# Panel_protection.net
KiCad netlist of a schematic drawn in Altium Designer
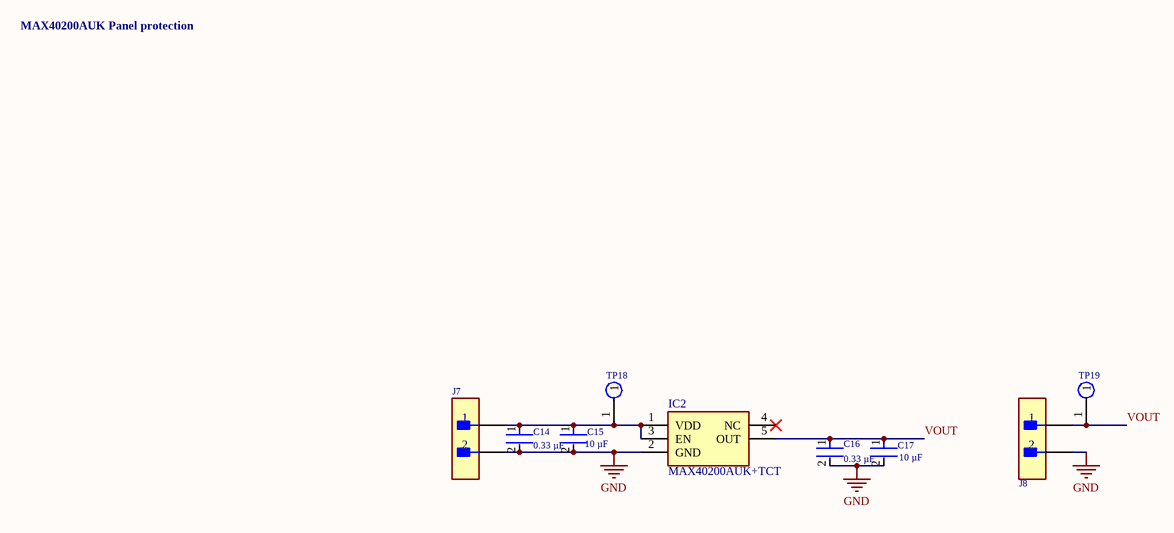
[diagram p0: Panel protection.SchDoc]

(export (version "E")
  (design (tool "Eeschema 10.0.6"))
  (components
    (comp (ref "C14")
      (value "0.33 µF")
      (footprint "FP-CC0603-DA-MFG")
      (description "CAP CER 0.33UF 16V X7R 0603CC0603KRX7R7BB334")
      (fields
        (field (name "OCTOPART") "https://octopart.com/cc0603krx7r7bb334-yageo-9291796")
        (field (name "MANUFACTURER") "YAGEO")
      )
      (libsource (lib "Altium Content Vault") (part "11868f565c42a9108669ba33697ecf6"))
    )
    (comp (ref "C15")
      (value "10 µF")
      (footprint "1206")
      (description "CC1206KKX5R7BB106 10 µF ±10% 16V Ceramic Capacitor X5R 1206 (3216 Metric)")
      (fields
        (field (name "OCTOPART") "https://octopart.com/c0603c223k4ractu-kemet-123286")
        (field (name "MANUFACTURER PART NUMBER") "C0603C223K4RACTU")
      )
      (libsource (lib "Capacitors") (part "CC1206KKX5R7BB106"))
    )
    (comp (ref "C16")
      (value "0.33 µF")
      (footprint "FP-CC0603-DA-MFG")
      (description "CAP CER 0.33UF 16V X7R 0603CC0603KRX7R7BB334")
      (fields
        (field (name "OCTOPART") "https://octopart.com/cc0603krx7r7bb334-yageo-9291796")
        (field (name "MANUFACTURER") "YAGEO")
      )
      (libsource (lib "Altium Content Vault") (part "11868f565c42a9108669ba33697ecf6"))
    )
    (comp (ref "C17")
      (value "10 µF")
      (footprint "1206")
      (description "CC1206KKX5R7BB106 10 µF ±10% 16V Ceramic Capacitor X5R 1206 (3216 Metric)")
      (fields
        (field (name "OCTOPART") "https://octopart.com/c0603c223k4ractu-kemet-123286")
        (field (name "MANUFACTURER PART NUMBER") "C0603C223K4RACTU")
      )
      (libsource (lib "Capacitors") (part "CC1206KKX5R7BB106"))
    )
    (comp (ref "IC2")
      (value "MAX40200AUK+TCT")
      (footprint "SamacSys:SOT95P280X145-5N")
      (description "Integrated Circuit")
      (libsource (lib "SamacSys") (part "MAX40200AUK+TCT"))
    )
    (comp (ref "J7")
      (value "B2B-XH-A(LF)(SN)")
      (footprint "FP-B2B-XH-A_LF_SN-MFG")
      (description "CONN HEADER VERT 2POS 2.5MM")
      (libsource (lib "Altium Content Vault") (part "3bc925449376181038e59eaffc5286c"))
    )
    (comp (ref "J8")
      (value "B2B-XH-A(LF)(SN)")
      (footprint "FP-B2B-XH-A_LF_SN-MFG")
      (description "CONN HEADER VERT 2POS 2.5MM")
      (libsource (lib "Altium Content Vault") (part "3bc925449376181038e59eaffc5286c"))
    )
    (comp (ref "TP18")
      (value "S2761-46R")
      (footprint "SamacSys:S276146R")
      (description "Test Point")
      (fields (field (name "MOUSER PART NUMBER") "855-S2761-46R"))
      (libsource (lib "SamacSys") (part "S2761-46R"))
    )
    (comp (ref "TP19")
      (value "S2761-46R")
      (footprint "SamacSys:S276146R")
      (description "Test Point")
      (fields (field (name "MOUSER PART NUMBER") "855-S2761-46R"))
      (libsource (lib "SamacSys") (part "S2761-46R"))
    )
  )
  (nets
    (net (code "1") (name "/VOUT") (class "Default")
      (node (ref "C16") (pin "1") (pinfunction "1_1") (pintype "passive"))
      (node (ref "C17") (pin "1") (pinfunction "1_1") (pintype "passive"))
      (node (ref "IC2") (pin "5") (pinfunction "OUT_5") (pintype "passive"))
      (node (ref "J8") (pin "1") (pinfunction "1_1") (pintype "passive"))
      (node (ref "TP19") (pin "1") (pinfunction "1_1") (pintype "passive"))
    )
    (net (code "2") (name "GND") (class "Default")
      (node (ref "C14") (pin "2") (pinfunction "2_2") (pintype "passive"))
      (node (ref "C15") (pin "2") (pinfunction "2_2") (pintype "passive"))
      (node (ref "C16") (pin "2") (pinfunction "2_2") (pintype "passive"))
      (node (ref "C17") (pin "2") (pinfunction "2_2") (pintype "passive"))
      (node (ref "IC2") (pin "2") (pinfunction "GND_2") (pintype "passive"))
      (node (ref "J7") (pin "2") (pinfunction "2_2") (pintype "passive"))
      (node (ref "J8") (pin "2") (pinfunction "2_2") (pintype "passive"))
    )
    (net (code "3") (name "Net-(IC2-EN)") (class "Default")
      (node (ref "C14") (pin "1") (pinfunction "1_1") (pintype "passive"))
      (node (ref "C15") (pin "1") (pinfunction "1_1") (pintype "passive"))
      (node (ref "IC2") (pin "1") (pinfunction "VDD_1") (pintype "passive"))
      (node (ref "IC2") (pin "3") (pinfunction "EN_3") (pintype "passive"))
      (node (ref "J7") (pin "1") (pinfunction "1_1") (pintype "passive"))
      (node (ref "TP18") (pin "1") (pinfunction "1_1") (pintype "passive"))
    )
    (net (code "4") (name "unconnected-(IC2-NC-Pad4)") (class "Default")
      (node (ref "IC2") (pin "4") (pinfunction "NC_4") (pintype "passive+no_connect"))
    )
  )
)
